# nrf52833-core.net
KiCad netlist of a schematic drawn in Altium Designer
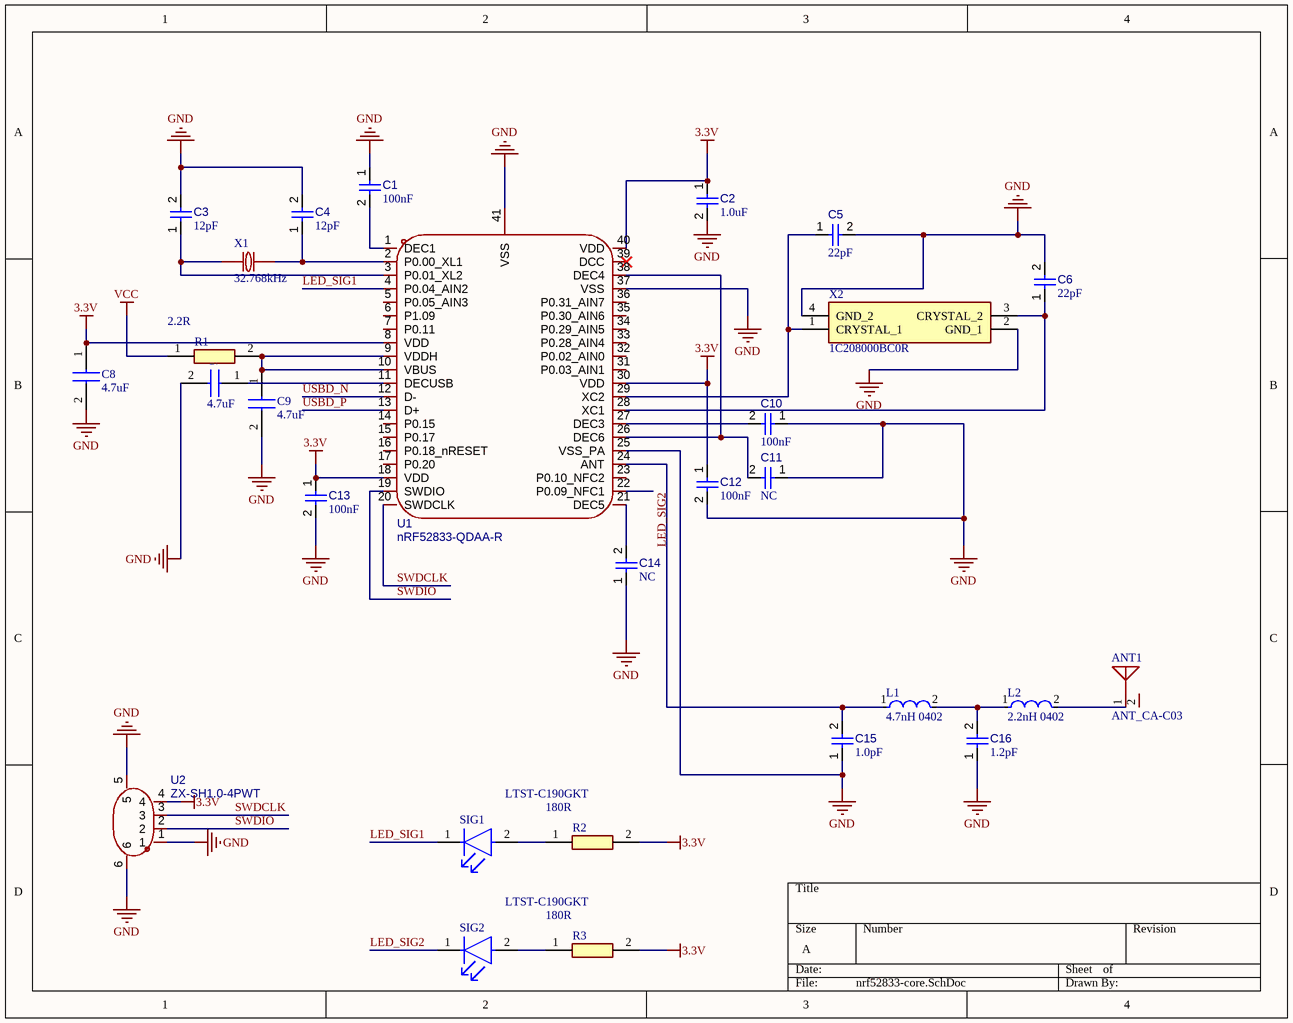
[diagram p0: nrf52833-core.SchDoc]

(export (version "E")
  (design (tool "Eeschema 10.0.6"))
  (components
    (comp (ref "ANT1")
      (value "ANT_CA-C03")
      (footprint "ANT-SMD_L5.5-W2.0")
      (libsource (lib "ApexNubLib") (part "ANT_CA-C03"))
    )
    (comp (ref "C1")
      (value "100nF")
      (footprint "CAPC1005X56X25ML10T15")
      (description "Chip Capacitor, 0.1 uF, +/- 5%, 16 V, 0402 (1005 Metric)")
      (fields (field (name "TOLERANCE") "5%") (field (name "Comment") "Capacitor 0.1 uF +/- 5% 16 V 0402"))
      (libsource (lib "ApexNubLib") (part "CMP-001-00001-4"))
    )
    (comp (ref "C2")
      (value "1.0uF")
      (footprint "CAPC1005X56X25ML10T15")
      (description "Chip Capacitor, 0.1 uF, +/- 5%, 16 V, 0402 (1005 Metric)")
      (fields (field (name "TOLERANCE") "5%") (field (name "Comment") "Capacitor 0.1 uF +/- 5% 16 V 0402"))
      (libsource (lib "ApexNubLib") (part "CMP-001-00001-4"))
    )
    (comp (ref "C3")
      (value "12pF")
      (footprint "CAPC0402(1005)33_L")
      (description "Chip Capacitor, 12pF +/-10%, 50V, 0402, Thickness 0.33 mm")
      (fields (field (name "TOLERANCE") "20%") (field (name "Comment") "Capacitor 12pF +/-10% 50V 0402"))
      (libsource (lib "ApexNubLib") (part "CMP-001-00072-2"))
    )
    (comp (ref "C4")
      (value "12pF")
      (footprint "CAPC0402(1005)33_L")
      (description "Chip Capacitor, 12pF +/-10%, 50V, 0402, Thickness 0.33 mm")
      (fields (field (name "TOLERANCE") "20%") (field (name "Comment") "Capacitor 12pF +/-10% 50V 0402"))
      (libsource (lib "ApexNubLib") (part "CMP-001-00072-2"))
    )
    (comp (ref "C5")
      (value "22pF")
      (footprint "CAPC0402(1005)33_L")
      (description "Chip Capacitor, 12pF +/-10%, 50V, 0402, Thickness 0.33 mm")
      (fields (field (name "TOLERANCE") "20%") (field (name "Comment") "Capacitor 12pF +/-10% 50V 0402"))
      (libsource (lib "ApexNubLib") (part "CMP-001-00072-2"))
    )
    (comp (ref "C6")
      (value "22pF")
      (footprint "CAPC0402(1005)33_L")
      (description "Chip Capacitor, 12pF +/-10%, 50V, 0402, Thickness 0.33 mm")
      (fields (field (name "TOLERANCE") "20%") (field (name "Comment") "Capacitor 12pF +/-10% 50V 0402"))
      (libsource (lib "ApexNubLib") (part "CMP-001-00072-2"))
    )
    (comp (ref "C7")
      (value "4.7uF")
      (footprint "CAPC1608X87N")
      (description "Capacitor")
      (fields (field (name "MANUFACTURER_PART_NUMBER") "C0603C100D5GACTU"))
      (libsource (lib "ApexNubLib") (part "C0603C100D5GACTU"))
    )
    (comp (ref "C8")
      (value "4.7uF")
      (footprint "CAPC1608X87N")
      (description "Capacitor")
      (fields (field (name "MANUFACTURER_PART_NUMBER") "C0603C100D5GACTU"))
      (libsource (lib "ApexNubLib") (part "C0603C100D5GACTU"))
    )
    (comp (ref "C9")
      (value "4.7uF")
      (footprint "CAPC1608X87N")
      (description "Capacitor")
      (fields (field (name "MANUFACTURER_PART_NUMBER") "C0603C100D5GACTU"))
      (libsource (lib "ApexNubLib") (part "C0603C100D5GACTU"))
    )
    (comp (ref "C10")
      (value "100nF")
      (footprint "CAPC1005X56X25ML10T15")
      (description "Chip Capacitor, 0.1 uF, +/- 5%, 16 V, 0402 (1005 Metric)")
      (fields (field (name "TOLERANCE") "5%") (field (name "Comment") "Capacitor 0.1 uF +/- 5% 16 V 0402"))
      (libsource (lib "ApexNubLib") (part "CMP-001-00001-4"))
    )
    (comp (ref "C11")
      (value "NC")
      (footprint "CAPC1005X56X25ML10T15")
      (description "Chip Capacitor, 0.1 uF, +/- 5%, 16 V, 0402 (1005 Metric)")
      (fields (field (name "TOLERANCE") "5%") (field (name "Comment") "Capacitor 0.1 uF +/- 5% 16 V 0402"))
      (libsource (lib "ApexNubLib") (part "CMP-001-00001-4"))
    )
    (comp (ref "C12")
      (value "100nF")
      (footprint "CAPC1005X56X25ML10T15")
      (description "Chip Capacitor, 0.1 uF, +/- 5%, 16 V, 0402 (1005 Metric)")
      (fields (field (name "TOLERANCE") "5%") (field (name "Comment") "Capacitor 0.1 uF +/- 5% 16 V 0402"))
      (libsource (lib "ApexNubLib") (part "CMP-001-00001-4"))
    )
    (comp (ref "C13")
      (value "100nF")
      (footprint "CAPC1005X56X25ML10T15")
      (description "Chip Capacitor, 0.1 uF, +/- 5%, 16 V, 0402 (1005 Metric)")
      (fields (field (name "TOLERANCE") "5%") (field (name "Comment") "Capacitor 0.1 uF +/- 5% 16 V 0402"))
      (libsource (lib "ApexNubLib") (part "CMP-001-00001-4"))
    )
    (comp (ref "C14")
      (value "NC")
      (footprint "CAPC1005X56X25ML10T15")
      (description "Chip Capacitor, 0.1 uF, +/- 5%, 16 V, 0402 (1005 Metric)")
      (fields (field (name "TOLERANCE") "5%") (field (name "Comment") "Capacitor 0.1 uF +/- 5% 16 V 0402"))
      (libsource (lib "ApexNubLib") (part "CMP-001-00001-4"))
    )
    (comp (ref "C15")
      (value "1.0pF")
      (footprint "CAPC0402(1005)33_L")
      (description "Chip Capacitor, 12pF +/-10%, 50V, 0402, Thickness 0.33 mm")
      (fields (field (name "TOLERANCE") "20%") (field (name "Comment") "Capacitor 12pF +/-10% 50V 0402"))
      (libsource (lib "Jacky Yuen") (part "CAP-NP-2"))
    )
    (comp (ref "C16")
      (value "1.2pF")
      (footprint "CAPC0402(1005)33_L")
      (description "Chip Capacitor, 12pF +/-10%, 50V, 0402, Thickness 0.33 mm")
      (fields (field (name "TOLERANCE") "20%") (field (name "Comment") "Capacitor 12pF +/-10% 50V 0402"))
      (libsource (lib "Jacky Yuen") (part "CAP-NP-2"))
    )
    (comp (ref "L1")
      (value "4.7nH 0402")
      (footprint "FP-LQW15AN_00-W0_6-0_1-MFG")
      (description "Wire Wound RF Inductor 5.8nH ±0.1nH 700mA 0.09Ω 0402 (1005)")
      (fields (field (name "TOLERANCE") "2%"))
      (libsource (lib "Altium Content Vault") (part "725321dda6339637d4d059423bc1c3c"))
    )
    (comp (ref "L2")
      (value "2.2nH 0402")
      (footprint "FP-LQW15AN_00-W0_6-0_1-MFG")
      (description "Wire Wound RF Inductor 5.8nH ±0.1nH 700mA 0.09Ω 0402 (1005)")
      (fields (field (name "TOLERANCE") "2%"))
      (libsource (lib "Altium Content Vault") (part "725321dda6339637d4d059423bc1c3c"))
    )
    (comp (ref "R1")
      (value "2.2R")
      (footprint "RESC1608X55N")
      (description "Resistor")
      (fields (field (name "MANUFACTURER_PART_NUMBER") "CPF0603B107KE"))
      (libsource (lib "ApexNubLib") (part "CPF0603B107KE"))
    )
    (comp (ref "R2")
      (value "180R")
      (footprint "RESC1608X55N")
      (description "Resistor")
      (fields (field (name "MANUFACTURER_PART_NUMBER") "CPF0603B107KE"))
      (libsource (lib "ApexNubLib") (part "CPF0603B107KE"))
    )
    (comp (ref "R3")
      (value "180R")
      (footprint "RESC1608X55N")
      (description "Resistor")
      (fields (field (name "MANUFACTURER_PART_NUMBER") "CPF0603B107KE"))
      (libsource (lib "ApexNubLib") (part "CPF0603B107KE"))
    )
    (comp (ref "SIG1")
      (value "LTST-C190GKT")
      (footprint "FP-LTST-C190GKT-MFG")
      (description "LED GREEN CLEAR CHIP SMD")
      (fields (field (name "VOLTAGE") "2V"))
      (libsource (lib "RARM 28 Drive Node") (part "CMP-22017-000005-2"))
    )
    (comp (ref "SIG2")
      (value "LTST-C190GKT")
      (footprint "FP-LTST-C190GKT-MFG")
      (description "LED GREEN CLEAR CHIP SMD")
      (fields (field (name "VOLTAGE") "2V"))
      (libsource (lib "RARM 28 Drive Node") (part "CMP-22017-000005-2"))
    )
    (comp (ref "U1")
      (value "nRF52833-QDAA-R")
      (footprint "QFN-40_L5.0-W5.0-P0.40-TL-EP3.6")
      (fields (field (name "MANUFACTURER") "NORDIC"))
      (libsource (lib "ApexNubLib") (part "nRF52833-QDAA-R"))
    )
    (comp (ref "U2")
      (value "ZX-SH1.0-4PWT")
      (footprint "CONN-SMD_4P-P1.00_MEGASTAR_ZX-SH1.0-4PWT")
      (fields (field (name "MANUFACTURER") "Megastar(兆星)"))
      (libsource (lib "ApexNubLib") (part "ZX-SH1.0-4PWT"))
    )
    (comp (ref "X1")
      (value "32.768kHz")
      (footprint "FC-135R_L3.2-W1.5")
      (fields (field (name "MANUFACTURER") "EPSON(爱普生)") (field (name "MANUFACTURER PART") "Q13FC13500004"))
      (libsource (lib "ApexNubLib") (part "Q13FC13500004_C32346"))
    )
    (comp (ref "X2")
      (value "1C208000BC0R")
      (footprint "SamacSys:1C208000BC0R")
      (description "Crystal or Oscillator")
      (libsource (lib "*") (part "1C208000BC0R"))
    )
  )
  (nets
    (net (code "1") (name "/LED_SIG1") (class "Default")
      (node (ref "SIG1") (pin "1") (pinfunction "C_1") (pintype "passive"))
      (node (ref "U1") (pin "4") (pinfunction "P0.04_AIN2_4") (pintype "passive"))
    )
    (net (code "2") (name "/LED_SIG2") (class "Default")
      (node (ref "SIG2") (pin "1") (pinfunction "C_1") (pintype "passive"))
      (node (ref "U1") (pin "22") (pinfunction "P0.09_NFC1_22") (pintype "passive"))
    )
    (net (code "3") (name "/SWDCLK") (class "Default")
      (node (ref "U1") (pin "20") (pinfunction "SWDCLK_20") (pintype "passive"))
      (node (ref "U2") (pin "3") (pinfunction "3_3") (pintype "passive"))
    )
    (net (code "4") (name "/SWDIO") (class "Default")
      (node (ref "U1") (pin "19") (pinfunction "SWDIO_19") (pintype "passive"))
      (node (ref "U2") (pin "2") (pinfunction "2_2") (pintype "passive"))
    )
    (net (code "5") (name "/USBD_N") (class "Default")
      (node (ref "U1") (pin "12") (pinfunction "D-_12") (pintype "passive"))
    )
    (net (code "6") (name "/USBD_P") (class "Default")
      (node (ref "U1") (pin "13") (pinfunction "D+_13") (pintype "passive"))
    )
    (net (code "7") (name "3.3V") (class "Default")
      (node (ref "C12") (pin "1") (pinfunction "1_1") (pintype "passive"))
      (node (ref "C13") (pin "1") (pinfunction "1_1") (pintype "passive"))
      (node (ref "C2") (pin "1") (pinfunction "1_1") (pintype "passive"))
      (node (ref "C8") (pin "1") (pinfunction "1_1") (pintype "passive"))
      (node (ref "R2") (pin "2") (pinfunction "2_2") (pintype "passive"))
      (node (ref "R3") (pin "2") (pinfunction "2_2") (pintype "passive"))
      (node (ref "U1") (pin "18") (pinfunction "VDD_18") (pintype "passive"))
      (node (ref "U1") (pin "30") (pinfunction "VDD_30") (pintype "passive"))
      (node (ref "U1") (pin "40") (pinfunction "VDD_40") (pintype "passive"))
      (node (ref "U1") (pin "8") (pinfunction "VDD_8") (pintype "passive"))
      (node (ref "U2") (pin "4") (pinfunction "4_4") (pintype "passive"))
    )
    (net (code "8") (name "GND") (class "Default")
      (node (ref "C1") (pin "1") (pinfunction "1_1") (pintype "passive"))
      (node (ref "C10") (pin "1") (pinfunction "1_1") (pintype "passive"))
      (node (ref "C11") (pin "1") (pinfunction "1_1") (pintype "passive"))
      (node (ref "C12") (pin "2") (pinfunction "2_2") (pintype "passive"))
      (node (ref "C13") (pin "2") (pinfunction "2_2") (pintype "passive"))
      (node (ref "C14") (pin "1") (pinfunction "1_1") (pintype "passive"))
      (node (ref "C15") (pin "1") (pinfunction "1_1") (pintype "passive"))
      (node (ref "C16") (pin "1") (pinfunction "1_1") (pintype "passive"))
      (node (ref "C2") (pin "2") (pinfunction "2_2") (pintype "passive"))
      (node (ref "C3") (pin "2") (pinfunction "2_2") (pintype "passive"))
      (node (ref "C4") (pin "2") (pinfunction "2_2") (pintype "passive"))
      (node (ref "C5") (pin "2") (pinfunction "2_2") (pintype "passive"))
      (node (ref "C6") (pin "2") (pinfunction "2_2") (pintype "passive"))
      (node (ref "C7") (pin "2") (pinfunction "2_2") (pintype "passive"))
      (node (ref "C8") (pin "2") (pinfunction "2_2") (pintype "passive"))
      (node (ref "C9") (pin "2") (pinfunction "2_2") (pintype "passive"))
      (node (ref "U1") (pin "25") (pinfunction "VSS_PA_25") (pintype "passive"))
      (node (ref "U1") (pin "37") (pinfunction "VSS_37") (pintype "passive"))
      (node (ref "U1") (pin "41") (pinfunction "VSS_41") (pintype "passive"))
      (node (ref "U2") (pin "1") (pinfunction "1_1") (pintype "passive"))
      (node (ref "U2") (pin "5") (pinfunction "5_5") (pintype "passive"))
      (node (ref "U2") (pin "6") (pinfunction "6_6") (pintype "passive"))
      (node (ref "X2") (pin "2") (pinfunction "GND_1_2") (pintype "passive"))
      (node (ref "X2") (pin "4") (pinfunction "GND_2_4") (pintype "passive"))
    )
    (net (code "9") (name "Net-(ANT1-Pad1)") (class "Default")
      (node (ref "ANT1") (pin "1") (pinfunction "1_1") (pintype "passive"))
      (node (ref "L2") (pin "2") (pinfunction "2_2") (pintype "passive"))
    )
    (net (code "10") (name "Net-(C16-Pad2)") (class "Default")
      (node (ref "C16") (pin "2") (pinfunction "2_2") (pintype "passive"))
      (node (ref "L1") (pin "2") (pinfunction "2_2") (pintype "passive"))
      (node (ref "L2") (pin "1") (pinfunction "1_1") (pintype "passive"))
    )
    (net (code "11") (name "Net-(SIG1-A)") (class "Default")
      (node (ref "R2") (pin "1") (pinfunction "1_1") (pintype "passive"))
      (node (ref "SIG1") (pin "2") (pinfunction "A_2") (pintype "passive"))
    )
    (net (code "12") (name "Net-(SIG2-A)") (class "Default")
      (node (ref "R3") (pin "1") (pinfunction "1_1") (pintype "passive"))
      (node (ref "SIG2") (pin "2") (pinfunction "A_2") (pintype "passive"))
    )
    (net (code "13") (name "Net-(U1-ANT)") (class "Default")
      (node (ref "C15") (pin "2") (pinfunction "2_2") (pintype "passive"))
      (node (ref "L1") (pin "1") (pinfunction "1_1") (pintype "passive"))
      (node (ref "U1") (pin "24") (pinfunction "ANT_24") (pintype "passive"))
    )
    (net (code "14") (name "Net-(U1-DEC1)") (class "Default")
      (node (ref "C1") (pin "2") (pinfunction "2_2") (pintype "passive"))
      (node (ref "U1") (pin "1") (pinfunction "DEC1_1") (pintype "passive"))
    )
    (net (code "15") (name "Net-(U1-DEC3)") (class "Default")
      (node (ref "C10") (pin "2") (pinfunction "2_2") (pintype "passive"))
      (node (ref "U1") (pin "27") (pinfunction "DEC3_27") (pintype "passive"))
    )
    (net (code "16") (name "Net-(U1-DEC4)") (class "Default")
      (node (ref "C11") (pin "2") (pinfunction "2_2") (pintype "passive"))
      (node (ref "U1") (pin "26") (pinfunction "DEC6_26") (pintype "passive"))
      (node (ref "U1") (pin "38") (pinfunction "DEC4_38") (pintype "passive"))
    )
    (net (code "17") (name "Net-(U1-DEC5)") (class "Default")
      (node (ref "C14") (pin "2") (pinfunction "2_2") (pintype "passive"))
      (node (ref "U1") (pin "21") (pinfunction "DEC5_21") (pintype "passive"))
    )
    (net (code "18") (name "Net-(U1-DECUSB)") (class "Default")
      (node (ref "C7") (pin "1") (pinfunction "1_1") (pintype "passive"))
      (node (ref "U1") (pin "11") (pinfunction "DECUSB_11") (pintype "passive"))
    )
    (net (code "19") (name "Net-(U1-P0.00_XL1)") (class "Default")
      (node (ref "C4") (pin "1") (pinfunction "1_1") (pintype "passive"))
      (node (ref "U1") (pin "2") (pinfunction "P0.00_XL1_2") (pintype "passive"))
      (node (ref "X1") (pin "2") (pinfunction "2_2") (pintype "passive"))
    )
    (net (code "20") (name "Net-(U1-P0.01_XL2)") (class "Default")
      (node (ref "C3") (pin "1") (pinfunction "1_1") (pintype "passive"))
      (node (ref "U1") (pin "3") (pinfunction "P0.01_XL2_3") (pintype "passive"))
      (node (ref "X1") (pin "1") (pinfunction "1_1") (pintype "passive"))
    )
    (net (code "21") (name "Net-(U1-VBUS)") (class "Default")
      (node (ref "C9") (pin "1") (pinfunction "1_1") (pintype "passive"))
      (node (ref "R1") (pin "2") (pinfunction "2_2") (pintype "passive"))
      (node (ref "U1") (pin "10") (pinfunction "VBUS_10") (pintype "passive"))
      (node (ref "U1") (pin "9") (pinfunction "VDDH_9") (pintype "passive"))
    )
    (net (code "22") (name "Net-(U1-XC1)") (class "Default")
      (node (ref "C6") (pin "1") (pinfunction "1_1") (pintype "passive"))
      (node (ref "U1") (pin "28") (pinfunction "XC1_28") (pintype "passive"))
      (node (ref "X2") (pin "3") (pinfunction "CRYSTAL_2_3") (pintype "passive"))
    )
    (net (code "23") (name "Net-(U1-XC2)") (class "Default")
      (node (ref "C5") (pin "1") (pinfunction "1_1") (pintype "passive"))
      (node (ref "U1") (pin "29") (pinfunction "XC2_29") (pintype "passive"))
      (node (ref "X2") (pin "1") (pinfunction "CRYSTAL_1_1") (pintype "passive"))
    )
    (net (code "24") (name "VCC") (class "Default")
      (node (ref "R1") (pin "1") (pinfunction "1_1") (pintype "passive"))
    )
    (net (code "25") (name "unconnected-(ANT1-NC-Pad2)") (class "Default")
      (node (ref "ANT1") (pin "2") (pinfunction "NC_2") (pintype "passive"))
    )
    (net (code "26") (name "unconnected-(U1-DCC-Pad39)") (class "Default")
      (node (ref "U1") (pin "39") (pinfunction "DCC_39") (pintype "passive+no_connect"))
    )
    (net (code "27") (name "unconnected-(U1-P0.02_AIN0-Pad32)") (class "Default")
      (node (ref "U1") (pin "32") (pinfunction "P0.02_AIN0_32") (pintype "passive"))
    )
    (net (code "28") (name "unconnected-(U1-P0.03_AIN1-Pad31)") (class "Default")
      (node (ref "U1") (pin "31") (pinfunction "P0.03_AIN1_31") (pintype "passive"))
    )
    (net (code "29") (name "unconnected-(U1-P0.05_AIN3-Pad5)") (class "Default")
      (node (ref "U1") (pin "5") (pinfunction "P0.05_AIN3_5") (pintype "passive"))
    )
    (net (code "30") (name "unconnected-(U1-P0.10_NFC2-Pad23)") (class "Default")
      (node (ref "U1") (pin "23") (pinfunction "P0.10_NFC2_23") (pintype "passive"))
    )
    (net (code "31") (name "unconnected-(U1-P0.11-Pad7)") (class "Default")
      (node (ref "U1") (pin "7") (pinfunction "P0.11_7") (pintype "passive"))
    )
    (net (code "32") (name "unconnected-(U1-P0.15-Pad14)") (class "Default")
      (node (ref "U1") (pin "14") (pinfunction "P0.15_14") (pintype "passive"))
    )
    (net (code "33") (name "unconnected-(U1-P0.17-Pad15)") (class "Default")
      (node (ref "U1") (pin "15") (pinfunction "P0.17_15") (pintype "passive"))
    )
    (net (code "34") (name "unconnected-(U1-P0.18_nRESET-Pad16)") (class "Default")
      (node (ref "U1") (pin "16") (pinfunction "P0.18_nRESET_16") (pintype "passive"))
    )
    (net (code "35") (name "unconnected-(U1-P0.20-Pad17)") (class "Default")
      (node (ref "U1") (pin "17") (pinfunction "P0.20_17") (pintype "passive"))
    )
    (net (code "36") (name "unconnected-(U1-P0.28_AIN4-Pad33)") (class "Default")
      (node (ref "U1") (pin "33") (pinfunction "P0.28_AIN4_33") (pintype "passive"))
    )
    (net (code "37") (name "unconnected-(U1-P0.29_AIN5-Pad34)") (class "Default")
      (node (ref "U1") (pin "34") (pinfunction "P0.29_AIN5_34") (pintype "passive"))
    )
    (net (code "38") (name "unconnected-(U1-P0.30_AIN6-Pad35)") (class "Default")
      (node (ref "U1") (pin "35") (pinfunction "P0.30_AIN6_35") (pintype "passive"))
    )
    (net (code "39") (name "unconnected-(U1-P0.31_AIN7-Pad36)") (class "Default")
      (node (ref "U1") (pin "36") (pinfunction "P0.31_AIN7_36") (pintype "passive"))
    )
    (net (code "40") (name "unconnected-(U1-P1.09-Pad6)") (class "Default")
      (node (ref "U1") (pin "6") (pinfunction "P1.09_6") (pintype "passive"))
    )
  )
)
